# sch.net
KiCad netlist of a schematic drawn in Altium Designer
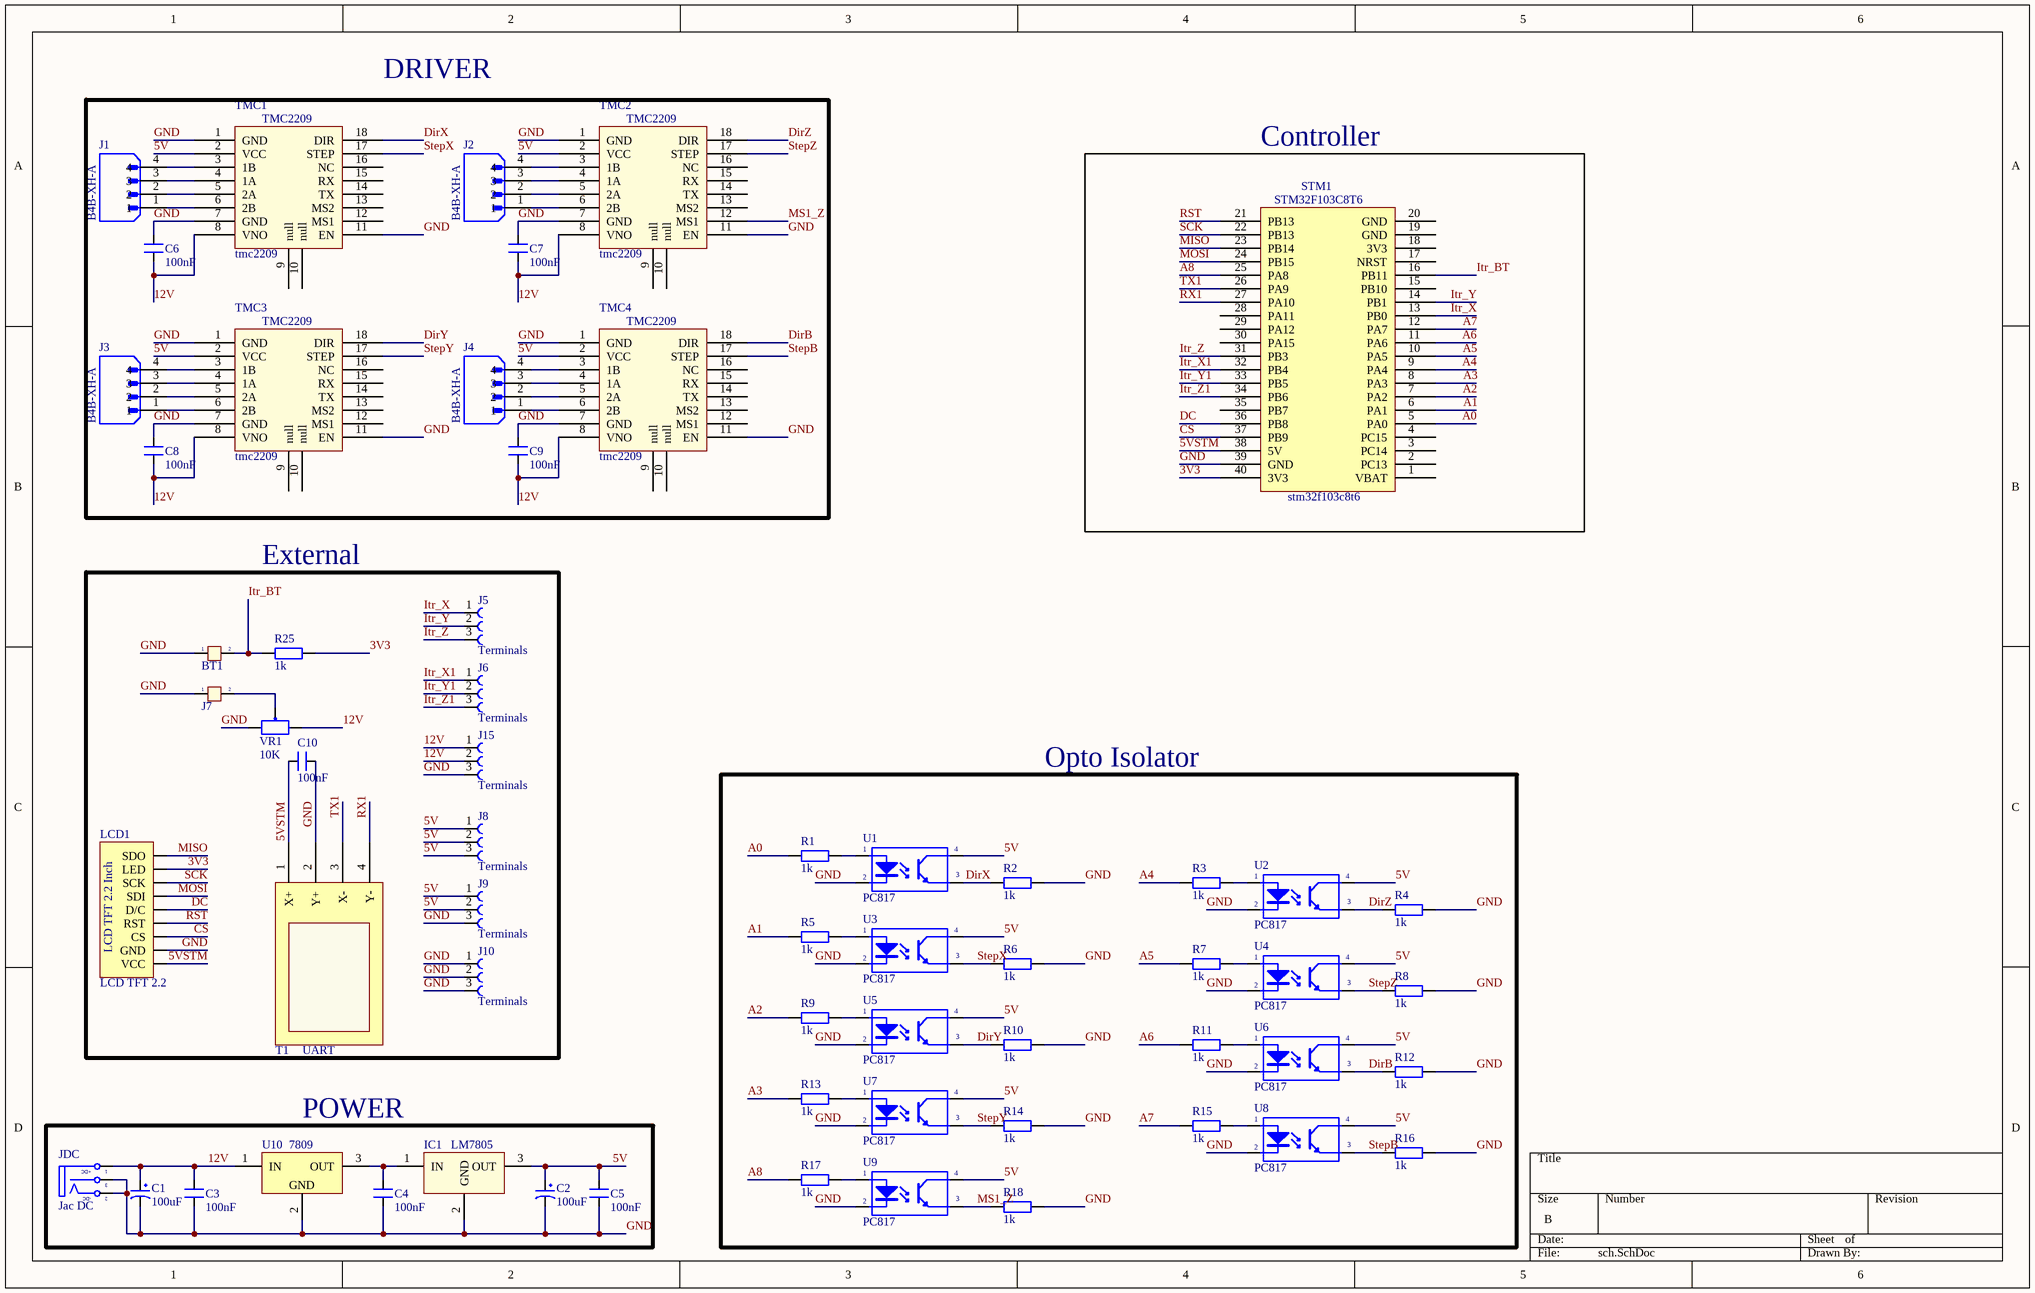
[diagram p0: sch.SchDoc]

(export (version "E")
  (design (tool "Eeschema 10.0.6"))
  (components
    (comp (ref "BT1") (value "Jumper 2") (footprint "jp2h") (libsource (lib "My Library") (part "JP 2")))
    (comp (ref "C1")
      (value "100uF")
      (footprint "CP1.5/3.4")
      (description "Cap 100uF/35V - 470uF/16V")
      (libsource (lib "My Library") (part "CP3"))
    )
    (comp (ref "C2")
      (value "100uF")
      (footprint "CP1.5/3.4")
      (description "Cap 100uF/35V - 470uF/16V")
      (libsource (lib "My Library") (part "CP3"))
    )
    (comp (ref "C3")
      (value "100nF")
      (footprint "CN2")
      (description "Cap np 104 => 105pF")
      (libsource (lib "My Library") (part "CN2"))
    )
    (comp (ref "C4")
      (value "100nF")
      (footprint "CN2")
      (description "Cap np 104 => 105pF")
      (libsource (lib "My Library") (part "CN2"))
    )
    (comp (ref "C5")
      (value "100nF")
      (footprint "CN2")
      (description "Cap np 104 => 105pF")
      (libsource (lib "My Library") (part "CN2"))
    )
    (comp (ref "C6")
      (value "100nF")
      (footprint "CN2")
      (description "Cap np 104 => 105pF")
      (libsource (lib "My Library") (part "CN2"))
    )
    (comp (ref "C7")
      (value "100nF")
      (footprint "CN2")
      (description "Cap np 104 => 105pF")
      (libsource (lib "My Library") (part "CN2"))
    )
    (comp (ref "C8")
      (value "100nF")
      (footprint "CN2")
      (description "Cap np 104 => 105pF")
      (libsource (lib "My Library") (part "CN2"))
    )
    (comp (ref "C9")
      (value "100nF")
      (footprint "CN2")
      (description "Cap np 104 => 105pF")
      (libsource (lib "My Library") (part "CN2"))
    )
    (comp (ref "C10")
      (value "100nF")
      (footprint "CN2")
      (description "Cap np 104 => 105pF")
      (libsource (lib "My Library") (part "CN2"))
    )
    (comp (ref "IC1")
      (value "LM7805")
      (footprint "QTO-220")
      (description "On ap +, from + 5 to + 24VDC")
      (libsource (lib "My Library") (part "LM78xx"))
    )
    (comp (ref "J1")
      (value "B4B-XH-A")
      (footprint "JST_B4B-XH-A(LF)(SN)")
      (fields (field (name "MP") "B4B-XH-A(LF)(SN)"))
      (libsource (lib "B4B-XH-A_LF__SN_") (part "B4B-XH-A(LF)(SN)"))
    )
    (comp (ref "J2")
      (value "B4B-XH-A")
      (footprint "JST_B4B-XH-A(LF)(SN)")
      (fields (field (name "MP") "B4B-XH-A(LF)(SN)"))
      (libsource (lib "B4B-XH-A_LF__SN_") (part "B4B-XH-A(LF)(SN)"))
    )
    (comp (ref "J3")
      (value "B4B-XH-A")
      (footprint "JST_B4B-XH-A(LF)(SN)")
      (fields (field (name "MP") "B4B-XH-A(LF)(SN)"))
      (libsource (lib "B4B-XH-A_LF__SN_") (part "B4B-XH-A(LF)(SN)"))
    )
    (comp (ref "J4")
      (value "B4B-XH-A")
      (footprint "JST_B4B-XH-A(LF)(SN)")
      (fields (field (name "MP") "B4B-XH-A(LF)(SN)"))
      (libsource (lib "B4B-XH-A_LF__SN_") (part "B4B-XH-A(LF)(SN)"))
    )
    (comp (ref "J5")
      (value "Terminals")
      (footprint "691214110003")
      (description "3 Position Wire to Board Terminal Block Horizontal with Board 0.138 (3.50mm) Through Hole")
      (fields (field (name "MP") "691214110003") (field (name "MF") "Wurth Elektronik"))
      (libsource (lib "691214110003") (part "691214110003"))
    )
    (comp (ref "J6")
      (value "Terminals")
      (footprint "691214110003")
      (description "3 Position Wire to Board Terminal Block Horizontal with Board 0.138 (3.50mm) Through Hole")
      (fields (field (name "MP") "691214110003") (field (name "MF") "Wurth Elektronik"))
      (libsource (lib "691214110003") (part "691214110003"))
    )
    (comp (ref "J7") (value "Jumper 2") (footprint "jp2h") (libsource (lib "syhaunguyen") (part "JP 2")))
    (comp (ref "J8")
      (value "Terminals")
      (footprint "691214110003")
      (description "3 Position Wire to Board Terminal Block Horizontal with Board 0.138 (3.50mm) Through Hole")
      (fields (field (name "MP") "691214110003") (field (name "MF") "Wurth Elektronik"))
      (libsource (lib "691214110003") (part "691214110003"))
    )
    (comp (ref "J9")
      (value "Terminals")
      (footprint "691214110003")
      (description "3 Position Wire to Board Terminal Block Horizontal with Board 0.138 (3.50mm) Through Hole")
      (fields (field (name "MP") "691214110003") (field (name "MF") "Wurth Elektronik"))
      (libsource (lib "691214110003") (part "691214110003"))
    )
    (comp (ref "J10")
      (value "Terminals")
      (footprint "691214110003")
      (description "3 Position Wire to Board Terminal Block Horizontal with Board 0.138 (3.50mm) Through Hole")
      (fields (field (name "MP") "691214110003") (field (name "MF") "Wurth Elektronik"))
      (libsource (lib "691214110003") (part "691214110003"))
    )
    (comp (ref "J15")
      (value "Terminals")
      (footprint "691214110003")
      (description "3 Position Wire to Board Terminal Block Horizontal with Board 0.138 (3.50mm) Through Hole")
      (fields (field (name "MP") "691214110003") (field (name "MF") "Wurth Elektronik"))
      (libsource (lib "691214110003") (part "691214110003"))
    )
    (comp (ref "JDC")
      (value "Jac DC")
      (footprint "DC-IN")
      (description "Jac DC input")
      (libsource (lib "My Library") (part "DCIN"))
    )
    (comp (ref "LCD1")
      (value "LCD TFT 2.2")
      (footprint "JP9-C1T")
      (fields
        (field (name "MANUFACTURER") "Würth Elektronik eiSos GmbH")
        (field (name "PARTNO") "613009143121")
        (field (name "CREATED BY") "Karrer Zheng")
      )
      (libsource (lib "My Library") (part "LCD TFT 2.2"))
    )
    (comp (ref "R1")
      (value "1k")
      (footprint "R1/4W")
      (description "Resistor 1/4W")
      (libsource (lib "My Library") (part "R1/4W"))
    )
    (comp (ref "R2")
      (value "1k")
      (footprint "R1/4W")
      (description "Resistor 1/4W")
      (libsource (lib "My Library") (part "R1/4W"))
    )
    (comp (ref "R3")
      (value "1k")
      (footprint "R1/4W")
      (description "Resistor 1/4W")
      (libsource (lib "My Library") (part "R1/4W"))
    )
    (comp (ref "R4")
      (value "1k")
      (footprint "R1/4W")
      (description "Resistor 1/4W")
      (libsource (lib "My Library") (part "R1/4W"))
    )
    (comp (ref "R5")
      (value "1k")
      (footprint "R1/4W")
      (description "Resistor 1/4W")
      (libsource (lib "My Library") (part "R1/4W"))
    )
    (comp (ref "R6")
      (value "1k")
      (footprint "R1/4W")
      (description "Resistor 1/4W")
      (libsource (lib "My Library") (part "R1/4W"))
    )
    (comp (ref "R7")
      (value "1k")
      (footprint "R1/4W")
      (description "Resistor 1/4W")
      (libsource (lib "My Library") (part "R1/4W"))
    )
    (comp (ref "R8")
      (value "1k")
      (footprint "R1/4W")
      (description "Resistor 1/4W")
      (libsource (lib "My Library") (part "R1/4W"))
    )
    (comp (ref "R9")
      (value "1k")
      (footprint "R1/4W")
      (description "Resistor 1/4W")
      (libsource (lib "My Library") (part "R1/4W"))
    )
    (comp (ref "R10")
      (value "1k")
      (footprint "R1/4W")
      (description "Resistor 1/4W")
      (libsource (lib "My Library") (part "R1/4W"))
    )
    (comp (ref "R11")
      (value "1k")
      (footprint "R1/4W")
      (description "Resistor 1/4W")
      (libsource (lib "My Library") (part "R1/4W"))
    )
    (comp (ref "R12")
      (value "1k")
      (footprint "R1/4W")
      (description "Resistor 1/4W")
      (libsource (lib "My Library") (part "R1/4W"))
    )
    (comp (ref "R13")
      (value "1k")
      (footprint "R1/4W")
      (description "Resistor 1/4W")
      (libsource (lib "My Library") (part "R1/4W"))
    )
    (comp (ref "R14")
      (value "1k")
      (footprint "R1/4W")
      (description "Resistor 1/4W")
      (libsource (lib "My Library") (part "R1/4W"))
    )
    (comp (ref "R15")
      (value "1k")
      (footprint "R1/4W")
      (description "Resistor 1/4W")
      (libsource (lib "My Library") (part "R1/4W"))
    )
    (comp (ref "R16")
      (value "1k")
      (footprint "R1/4W")
      (description "Resistor 1/4W")
      (libsource (lib "My Library") (part "R1/4W"))
    )
    (comp (ref "R17")
      (value "1k")
      (footprint "R1/4W")
      (description "Resistor 1/4W")
      (libsource (lib "My Library") (part "R1/4W"))
    )
    (comp (ref "R18")
      (value "1k")
      (footprint "R1/4W")
      (description "Resistor 1/4W")
      (libsource (lib "My Library") (part "R1/4W"))
    )
    (comp (ref "R25")
      (value "1k")
      (footprint "R1/4W")
      (description "Resistor 1/4W")
      (libsource (lib "My Library") (part "R1/4W"))
    )
    (comp (ref "STM1")
      (value "stm32f103c8t6")
      (footprint "STM32F103")
      (libsource (lib "STM32F103") (part "STM32F103"))
    )
    (comp (ref "T1")
      (value "UART")
      (footprint "HDR1X4H")
      (description "4 wires")
      (fields (field (name "CREATOR") "Nguyen Ba Bien"))
      (libsource (lib "My Library") (part "TouchPanel"))
    )
    (comp (ref "TMC1")
      (value "tmc2209")
      (footprint "TMC2209")
      (libsource (lib "tmc2209") (part "Driver_TMC2209"))
    )
    (comp (ref "TMC2")
      (value "tmc2209")
      (footprint "TMC2209")
      (libsource (lib "tmc2209") (part "Driver_TMC2209"))
    )
    (comp (ref "TMC3")
      (value "tmc2209")
      (footprint "TMC2209")
      (libsource (lib "tmc2209") (part "Driver_TMC2209"))
    )
    (comp (ref "TMC4")
      (value "tmc2209")
      (footprint "TMC2209")
      (libsource (lib "tmc2209") (part "Driver_TMC2209"))
    )
    (comp (ref "U1")
      (value "PC817")
      (footprint "DIP4/W0.3")
      (description "Single Opto")
      (libsource (lib "syhaunguyen") (part "PC817"))
    )
    (comp (ref "U2")
      (value "PC817")
      (footprint "DIP4/W0.3")
      (description "Single Opto")
      (libsource (lib "syhaunguyen") (part "PC817"))
    )
    (comp (ref "U3")
      (value "PC817")
      (footprint "DIP4/W0.3")
      (description "Single Opto")
      (libsource (lib "syhaunguyen") (part "PC817"))
    )
    (comp (ref "U4")
      (value "PC817")
      (footprint "DIP4/W0.3")
      (description "Single Opto")
      (libsource (lib "syhaunguyen") (part "PC817"))
    )
    (comp (ref "U5")
      (value "PC817")
      (footprint "DIP4/W0.3")
      (description "Single Opto")
      (libsource (lib "syhaunguyen") (part "PC817"))
    )
    (comp (ref "U6")
      (value "PC817")
      (footprint "DIP4/W0.3")
      (description "Single Opto")
      (libsource (lib "syhaunguyen") (part "PC817"))
    )
    (comp (ref "U7")
      (value "PC817")
      (footprint "DIP4/W0.3")
      (description "Single Opto")
      (libsource (lib "syhaunguyen") (part "PC817"))
    )
    (comp (ref "U8")
      (value "PC817")
      (footprint "DIP4/W0.3")
      (description "Single Opto")
      (libsource (lib "syhaunguyen") (part "PC817"))
    )
    (comp (ref "U9")
      (value "PC817")
      (footprint "DIP4/W0.3")
      (description "Single Opto")
      (libsource (lib "syhaunguyen") (part "PC817"))
    )
    (comp (ref "U10")
      (value "7809")
      (footprint "HDR1x3 BIG")
      (description "Positive Voltage Regulator")
      (fields (field (name "PUBLISHER") "Altium Limited"))
      (libsource (lib "My Library") (part "7809"))
    )
    (comp (ref "VR1")
      (value "10K")
      (footprint "VR")
      (description "Var Resistor")
      (libsource (lib "syhaunguyen") (part "VR"))
    )
  )
  (nets
    (net (code "1") (name "/3V3") (class "Default")
      (node (ref "LCD1") (pin "8") (pinfunction "LED_8") (pintype "passive"))
      (node (ref "R25") (pin "2") (pinfunction "2_2") (pintype "passive"))
      (node (ref "STM1") (pin "40") (pinfunction "3V3_40") (pintype "passive"))
    )
    (net (code "2") (name "/5V") (class "Default")
      (node (ref "C2") (pin "1") (pinfunction "1_1") (pintype "passive"))
      (node (ref "C5") (pin "2") (pinfunction "2_2") (pintype "passive"))
      (node (ref "IC1") (pin "3") (pinfunction "OUT_3") (pintype "passive"))
      (node (ref "J8") (pin "1") (pinfunction "1_1") (pintype "passive"))
      (node (ref "J8") (pin "2") (pinfunction "2_2") (pintype "passive"))
      (node (ref "J8") (pin "3") (pinfunction "3_3") (pintype "passive"))
      (node (ref "J9") (pin "1") (pinfunction "1_1") (pintype "passive"))
      (node (ref "J9") (pin "2") (pinfunction "2_2") (pintype "passive"))
      (node (ref "TMC1") (pin "2") (pinfunction "VCC_2") (pintype "passive"))
      (node (ref "TMC2") (pin "2") (pinfunction "VCC_2") (pintype "passive"))
      (node (ref "TMC3") (pin "2") (pinfunction "VCC_2") (pintype "passive"))
      (node (ref "TMC4") (pin "2") (pinfunction "VCC_2") (pintype "passive"))
      (node (ref "U1") (pin "4") (pinfunction "C_4") (pintype "passive"))
      (node (ref "U2") (pin "4") (pinfunction "C_4") (pintype "passive"))
      (node (ref "U3") (pin "4") (pinfunction "C_4") (pintype "passive"))
      (node (ref "U4") (pin "4") (pinfunction "C_4") (pintype "passive"))
      (node (ref "U5") (pin "4") (pinfunction "C_4") (pintype "passive"))
      (node (ref "U6") (pin "4") (pinfunction "C_4") (pintype "passive"))
      (node (ref "U7") (pin "4") (pinfunction "C_4") (pintype "passive"))
      (node (ref "U8") (pin "4") (pinfunction "C_4") (pintype "passive"))
      (node (ref "U9") (pin "4") (pinfunction "C_4") (pintype "passive"))
    )
    (net (code "3") (name "/5VSTM") (class "Default")
      (node (ref "C10") (pin "2") (pinfunction "2_2") (pintype "passive"))
      (node (ref "LCD1") (pin "1") (pinfunction "VCC_1") (pintype "passive"))
      (node (ref "STM1") (pin "38") (pinfunction "5V_38") (pintype "passive"))
      (node (ref "T1") (pin "1") (pinfunction "X+_1") (pintype "passive"))
    )
    (net (code "4") (name "/12V") (class "Default")
      (node (ref "C1") (pin "1") (pinfunction "1_1") (pintype "passive"))
      (node (ref "C3") (pin "2") (pinfunction "2_2") (pintype "passive"))
      (node (ref "C6") (pin "1") (pinfunction "1_1") (pintype "passive"))
      (node (ref "C7") (pin "1") (pinfunction "1_1") (pintype "passive"))
      (node (ref "C8") (pin "1") (pinfunction "1_1") (pintype "passive"))
      (node (ref "C9") (pin "1") (pinfunction "1_1") (pintype "passive"))
      (node (ref "J15") (pin "1") (pinfunction "1_1") (pintype "passive"))
      (node (ref "J15") (pin "2") (pinfunction "2_2") (pintype "passive"))
      (node (ref "JDC") (pin "1") (pinfunction "T_1") (pintype "passive"))
      (node (ref "TMC1") (pin "8") (pinfunction "VNO_8") (pintype "passive"))
      (node (ref "TMC2") (pin "8") (pinfunction "VNO_8") (pintype "passive"))
      (node (ref "TMC3") (pin "8") (pinfunction "VNO_8") (pintype "passive"))
      (node (ref "TMC4") (pin "8") (pinfunction "VNO_8") (pintype "passive"))
      (node (ref "U10") (pin "1") (pinfunction "IN_1") (pintype "power_in"))
      (node (ref "VR1") (pin "3") (pinfunction "3_3") (pintype "passive"))
    )
    (net (code "5") (name "/A0") (class "Default")
      (node (ref "R1") (pin "1") (pinfunction "1_1") (pintype "passive"))
      (node (ref "STM1") (pin "5") (pinfunction "PA0_5") (pintype "passive"))
    )
    (net (code "6") (name "/A1") (class "Default")
      (node (ref "R5") (pin "1") (pinfunction "1_1") (pintype "passive"))
      (node (ref "STM1") (pin "6") (pinfunction "PA1_6") (pintype "passive"))
    )
    (net (code "7") (name "/A2") (class "Default")
      (node (ref "R9") (pin "1") (pinfunction "1_1") (pintype "passive"))
      (node (ref "STM1") (pin "7") (pinfunction "PA2_7") (pintype "passive"))
    )
    (net (code "8") (name "/A3") (class "Default")
      (node (ref "R13") (pin "1") (pinfunction "1_1") (pintype "passive"))
      (node (ref "STM1") (pin "8") (pinfunction "PA3_8") (pintype "passive"))
    )
    (net (code "9") (name "/A4") (class "Default")
      (node (ref "R3") (pin "1") (pinfunction "1_1") (pintype "passive"))
      (node (ref "STM1") (pin "9") (pinfunction "PA4_9") (pintype "passive"))
    )
    (net (code "10") (name "/A5") (class "Default")
      (node (ref "R7") (pin "1") (pinfunction "1_1") (pintype "passive"))
      (node (ref "STM1") (pin "10") (pinfunction "PA5_10") (pintype "passive"))
    )
    (net (code "11") (name "/A6") (class "Default")
      (node (ref "R11") (pin "1") (pinfunction "1_1") (pintype "passive"))
      (node (ref "STM1") (pin "11") (pinfunction "PA6_11") (pintype "passive"))
    )
    (net (code "12") (name "/A7") (class "Default")
      (node (ref "R15") (pin "1") (pinfunction "1_1") (pintype "passive"))
      (node (ref "STM1") (pin "12") (pinfunction "PA7_12") (pintype "passive"))
    )
    (net (code "13") (name "/A8") (class "Default")
      (node (ref "R17") (pin "1") (pinfunction "1_1") (pintype "passive"))
      (node (ref "STM1") (pin "25") (pinfunction "PA8_25") (pintype "passive"))
    )
    (net (code "14") (name "/CS") (class "Default")
      (node (ref "LCD1") (pin "3") (pinfunction "CS_3") (pintype "passive"))
      (node (ref "STM1") (pin "37") (pinfunction "PB9_37") (pintype "passive"))
    )
    (net (code "15") (name "/DC") (class "Default")
      (node (ref "LCD1") (pin "5") (pinfunction "D/C_5") (pintype "passive"))
      (node (ref "STM1") (pin "36") (pinfunction "PB8_36") (pintype "passive"))
    )
    (net (code "16") (name "/DirB") (class "Default")
      (node (ref "R12") (pin "1") (pinfunction "1_1") (pintype "passive"))
      (node (ref "TMC4") (pin "18") (pinfunction "DIR_18") (pintype "passive"))
      (node (ref "U6") (pin "3") (pinfunction "E_3") (pintype "passive"))
    )
    (net (code "17") (name "/DirX") (class "Default")
      (node (ref "R2") (pin "1") (pinfunction "1_1") (pintype "passive"))
      (node (ref "TMC1") (pin "18") (pinfunction "DIR_18") (pintype "passive"))
      (node (ref "U1") (pin "3") (pinfunction "E_3") (pintype "passive"))
    )
    (net (code "18") (name "/DirY") (class "Default")
      (node (ref "R10") (pin "1") (pinfunction "1_1") (pintype "passive"))
      (node (ref "TMC3") (pin "18") (pinfunction "DIR_18") (pintype "passive"))
      (node (ref "U5") (pin "3") (pinfunction "E_3") (pintype "passive"))
    )
    (net (code "19") (name "/DirZ") (class "Default")
      (node (ref "R4") (pin "1") (pinfunction "1_1") (pintype "passive"))
      (node (ref "TMC2") (pin "18") (pinfunction "DIR_18") (pintype "passive"))
      (node (ref "U2") (pin "3") (pinfunction "E_3") (pintype "passive"))
    )
    (net (code "20") (name "/GND") (class "Default")
      (node (ref "BT1") (pin "1") (pinfunction "1_1") (pintype "passive"))
      (node (ref "C1") (pin "2") (pinfunction "2_2") (pintype "passive"))
      (node (ref "C10") (pin "1") (pinfunction "1_1") (pintype "passive"))
      (node (ref "C2") (pin "2") (pinfunction "2_2") (pintype "passive"))
      (node (ref "C3") (pin "1") (pinfunction "1_1") (pintype "passive"))
      (node (ref "C4") (pin "1") (pinfunction "1_1") (pintype "passive"))
      (node (ref "C5") (pin "1") (pinfunction "1_1") (pintype "passive"))
      (node (ref "C6") (pin "2") (pinfunction "2_2") (pintype "passive"))
      (node (ref "C7") (pin "2") (pinfunction "2_2") (pintype "passive"))
      (node (ref "C8") (pin "2") (pinfunction "2_2") (pintype "passive"))
      (node (ref "C9") (pin "2") (pinfunction "2_2") (pintype "passive"))
      (node (ref "IC1") (pin "2") (pinfunction "GND_2") (pintype "passive"))
      (node (ref "J10") (pin "1") (pinfunction "1_1") (pintype "passive"))
      (node (ref "J10") (pin "2") (pinfunction "2_2") (pintype "passive"))
      (node (ref "J10") (pin "3") (pinfunction "3_3") (pintype "passive"))
      (node (ref "J15") (pin "3") (pinfunction "3_3") (pintype "passive"))
      (node (ref "J7") (pin "1") (pinfunction "1_1") (pintype "passive"))
      (node (ref "J9") (pin "3") (pinfunction "3_3") (pintype "passive"))
      (node (ref "JDC") (pin "2") (pinfunction "TN_2") (pintype "passive"))
      (node (ref "JDC") (pin "3") (pinfunction "S_3") (pintype "power_in"))
      (node (ref "LCD1") (pin "2") (pinfunction "GND_2") (pintype "passive"))
      (node (ref "R10") (pin "2") (pinfunction "2_2") (pintype "passive"))
      (node (ref "R12") (pin "2") (pinfunction "2_2") (pintype "passive"))
      (node (ref "R14") (pin "2") (pinfunction "2_2") (pintype "passive"))
      (node (ref "R16") (pin "2") (pinfunction "2_2") (pintype "passive"))
      (node (ref "R18") (pin "2") (pinfunction "2_2") (pintype "passive"))
      (node (ref "R2") (pin "2") (pinfunction "2_2") (pintype "passive"))
      (node (ref "R4") (pin "2") (pinfunction "2_2") (pintype "passive"))
      (node (ref "R6") (pin "2") (pinfunction "2_2") (pintype "passive"))
      (node (ref "R8") (pin "2") (pinfunction "2_2") (pintype "passive"))
      (node (ref "STM1") (pin "39") (pinfunction "GND_39") (pintype "passive"))
      (node (ref "T1") (pin "2") (pinfunction "Y+_2") (pintype "passive"))
      (node (ref "TMC1") (pin "1") (pinfunction "GND_1") (pintype "passive"))
      (node (ref "TMC1") (pin "11") (pinfunction "EN_11") (pintype "passive"))
      (node (ref "TMC1") (pin "7") (pinfunction "GND_7") (pintype "passive"))
      (node (ref "TMC2") (pin "1") (pinfunction "GND_1") (pintype "passive"))
      (node (ref "TMC2") (pin "11") (pinfunction "EN_11") (pintype "passive"))
      (node (ref "TMC2") (pin "7") (pinfunction "GND_7") (pintype "passive"))
      (node (ref "TMC3") (pin "1") (pinfunction "GND_1") (pintype "passive"))
      (node (ref "TMC3") (pin "11") (pinfunction "EN_11") (pintype "passive"))
      (node (ref "TMC3") (pin "7") (pinfunction "GND_7") (pintype "passive"))
      (node (ref "TMC4") (pin "1") (pinfunction "GND_1") (pintype "passive"))
      (node (ref "TMC4") (pin "11") (pinfunction "EN_11") (pintype "passive"))
      (node (ref "TMC4") (pin "7") (pinfunction "GND_7") (pintype "passive"))
      (node (ref "U1") (pin "2") (pinfunction "K_2") (pintype "passive"))
      (node (ref "U10") (pin "2") (pinfunction "GND_2") (pintype "power_in"))
      (node (ref "U2") (pin "2") (pinfunction "K_2") (pintype "passive"))
      (node (ref "U3") (pin "2") (pinfunction "K_2") (pintype "passive"))
      (node (ref "U4") (pin "2") (pinfunction "K_2") (pintype "passive"))
      (node (ref "U5") (pin "2") (pinfunction "K_2") (pintype "passive"))
      (node (ref "U6") (pin "2") (pinfunction "K_2") (pintype "passive"))
      (node (ref "U7") (pin "2") (pinfunction "K_2") (pintype "passive"))
      (node (ref "U8") (pin "2") (pinfunction "K_2") (pintype "passive"))
      (node (ref "U9") (pin "2") (pinfunction "K_2") (pintype "passive"))
      (node (ref "VR1") (pin "1") (pinfunction "1_1") (pintype "passive"))
    )
    (net (code "21") (name "/Itr_BT") (class "Default")
      (node (ref "BT1") (pin "2") (pinfunction "2_2") (pintype "passive"))
      (node (ref "R25") (pin "1") (pinfunction "1_1") (pintype "passive"))
      (node (ref "STM1") (pin "16") (pinfunction "PB11_16") (pintype "passive"))
    )
    (net (code "22") (name "/Itr_X") (class "Default")
      (node (ref "J5") (pin "1") (pinfunction "1_1") (pintype "passive"))
      (node (ref "STM1") (pin "13") (pinfunction "PB0_13") (pintype "passive"))
    )
    (net (code "23") (name "/Itr_X1") (class "Default")
      (node (ref "J6") (pin "1") (pinfunction "1_1") (pintype "passive"))
      (node (ref "STM1") (pin "32") (pinfunction "PB4_32") (pintype "passive"))
    )
    (net (code "24") (name "/Itr_Y") (class "Default")
      (node (ref "J5") (pin "2") (pinfunction "2_2") (pintype "passive"))
      (node (ref "STM1") (pin "14") (pinfunction "PB1_14") (pintype "passive"))
    )
    (net (code "25") (name "/Itr_Y1") (class "Default")
      (node (ref "J6") (pin "2") (pinfunction "2_2") (pintype "passive"))
      (node (ref "STM1") (pin "33") (pinfunction "PB5_33") (pintype "passive"))
    )
    (net (code "26") (name "/Itr_Z") (class "Default")
      (node (ref "J5") (pin "3") (pinfunction "3_3") (pintype "passive"))
      (node (ref "STM1") (pin "31") (pinfunction "PB3_31") (pintype "passive"))
    )
    (net (code "27") (name "/Itr_Z1") (class "Default")
      (node (ref "J6") (pin "3") (pinfunction "3_3") (pintype "passive"))
      (node (ref "STM1") (pin "34") (pinfunction "PB6_34") (pintype "passive"))
    )
    (net (code "28") (name "/MISO") (class "Default")
      (node (ref "LCD1") (pin "9") (pinfunction "SDO_9") (pintype "passive"))
      (node (ref "STM1") (pin "23") (pinfunction "PB14_23") (pintype "passive"))
    )
    (net (code "29") (name "/MOSI") (class "Default")
      (node (ref "LCD1") (pin "6") (pinfunction "SDI_6") (pintype "passive"))
      (node (ref "STM1") (pin "24") (pinfunction "PB15_24") (pintype "passive"))
    )
    (net (code "30") (name "/MS1_Z") (class "Default")
      (node (ref "R18") (pin "1") (pinfunction "1_1") (pintype "passive"))
      (node (ref "TMC2") (pin "12") (pinfunction "MS1_12") (pintype "passive"))
      (node (ref "U9") (pin "3") (pinfunction "E_3") (pintype "passive"))
    )
    (net (code "31") (name "/RST") (class "Default")
      (node (ref "LCD1") (pin "4") (pinfunction "RST_4") (pintype "passive"))
      (node (ref "STM1") (pin "21") (pinfunction "PB13_21") (pintype "passive"))
    )
    (net (code "32") (name "/RX1") (class "Default")
      (node (ref "STM1") (pin "27") (pinfunction "PA10_27") (pintype "passive"))
      (node (ref "T1") (pin "4") (pinfunction "Y-_4") (pintype "passive"))
    )
    (net (code "33") (name "/SCK") (class "Default")
      (node (ref "LCD1") (pin "7") (pinfunction "SCK_7") (pintype "passive"))
      (node (ref "STM1") (pin "22") (pinfunction "PB13_22") (pintype "passive"))
    )
    (net (code "34") (name "/StepB") (class "Default")
      (node (ref "R16") (pin "1") (pinfunction "1_1") (pintype "passive"))
      (node (ref "TMC4") (pin "17") (pinfunction "STEP_17") (pintype "passive"))
      (node (ref "U8") (pin "3") (pinfunction "E_3") (pintype "passive"))
    )
    (net (code "35") (name "/StepX") (class "Default")
      (node (ref "R6") (pin "1") (pinfunction "1_1") (pintype "passive"))
      (node (ref "TMC1") (pin "17") (pinfunction "STEP_17") (pintype "passive"))
      (node (ref "U3") (pin "3") (pinfunction "E_3") (pintype "passive"))
    )
    (net (code "36") (name "/StepY") (class "Default")
      (node (ref "R14") (pin "1") (pinfunction "1_1") (pintype "passive"))
      (node (ref "TMC3") (pin "17") (pinfunction "STEP_17") (pintype "passive"))
      (node (ref "U7") (pin "3") (pinfunction "E_3") (pintype "passive"))
    )
    (net (code "37") (name "/StepZ") (class "Default")
      (node (ref "R8") (pin "1") (pinfunction "1_1") (pintype "passive"))
      (node (ref "TMC2") (pin "17") (pinfunction "STEP_17") (pintype "passive"))
      (node (ref "U4") (pin "3") (pinfunction "E_3") (pintype "passive"))
    )
    (net (code "38") (name "/TX1") (class "Default")
      (node (ref "STM1") (pin "26") (pinfunction "PA9_26") (pintype "passive"))
      (node (ref "T1") (pin "3") (pinfunction "X-_3") (pintype "passive"))
    )
    (net (code "39") (name "Net-(IC1-IN)") (class "Default")
      (node (ref "C4") (pin "2") (pinfunction "2_2") (pintype "passive"))
      (node (ref "IC1") (pin "1") (pinfunction "IN_1") (pintype "passive"))
      (node (ref "U10") (pin "3") (pinfunction "OUT_3") (pintype "power_in"))
    )
    (net (code "40") (name "Net-(J7-Pad2)") (class "Default")
      (node (ref "J7") (pin "2") (pinfunction "2_2") (pintype "passive"))
      (node (ref "VR1") (pin "2") (pinfunction "2_2") (pintype "passive"))
    )
    (net (code "41") (name "Net-(TMC1-1A)") (class "Default")
      (node (ref "J1") (pin "3") (pinfunction "3_3") (pintype "passive"))
      (node (ref "TMC1") (pin "4") (pinfunction "1A_4") (pintype "passive"))
    )
    (net (code "42") (name "Net-(TMC1-1B)") (class "Default")
      (node (ref "J1") (pin "4") (pinfunction "4_4") (pintype "passive"))
      (node (ref "TMC1") (pin "3") (pinfunction "1B_3") (pintype "passive"))
    )
    (net (code "43") (name "Net-(TMC1-2A)") (class "Default")
      (node (ref "J1") (pin "2") (pinfunction "2_2") (pintype "passive"))
      (node (ref "TMC1") (pin "5") (pinfunction "2A_5") (pintype "passive"))
    )
    (net (code "44") (name "Net-(TMC1-2B)") (class "Default")
      (node (ref "J1") (pin "1") (pinfunction "1_1") (pintype "passive"))
      (node (ref "TMC1") (pin "6") (pinfunction "2B_6") (pintype "passive"))
    )
    (net (code "45") (name "Net-(TMC2-1A)") (class "Default")
      (node (ref "J2") (pin "3") (pinfunction "3_3") (pintype "passive"))
      (node (ref "TMC2") (pin "4") (pinfunction "1A_4") (pintype "passive"))
    )
    (net (code "46") (name "Net-(TMC2-1B)") (class "Default")
      (node (ref "J2") (pin "4") (pinfunction "4_4") (pintype "passive"))
      (node (ref "TMC2") (pin "3") (pinfunction "1B_3") (pintype "passive"))
    )
    (net (code "47") (name "Net-(TMC2-2A)") (class "Default")
      (node (ref "J2") (pin "2") (pinfunction "2_2") (pintype "passive"))
      (node (ref "TMC2") (pin "5") (pinfunction "2A_5") (pintype "passive"))
    )
    (net (code "48") (name "Net-(TMC2-2B)") (class "Default")
      (node (ref "J2") (pin "1") (pinfunction "1_1") (pintype "passive"))
      (node (ref "TMC2") (pin "6") (pinfunction "2B_6") (pintype "passive"))
    )
    (net (code "49") (name "Net-(TMC3-1A)") (class "Default")
      (node (ref "J3") (pin "3") (pinfunction "3_3") (pintype "passive"))
      (node (ref "TMC3") (pin "4") (pinfunction "1A_4") (pintype "passive"))
    )
    (net (code "50") (name "Net-(TMC3-1B)") (class "Default")
      (node (ref "J3") (pin "4") (pinfunction "4_4") (pintype "passive"))
      (node (ref "TMC3") (pin "3") (pinfunction "1B_3") (pintype "passive"))
    )
    (net (code "51") (name "Net-(TMC3-2A)") (class "Default")
      (node (ref "J3") (pin "2") (pinfunction "2_2") (pintype "passive"))
      (node (ref "TMC3") (pin "5") (pinfunction "2A_5") (pintype "passive"))
    )
    (net (code "52") (name "Net-(TMC3-2B)") (class "Default")
      (node (ref "J3") (pin "1") (pinfunction "1_1") (pintype "passive"))
      (node (ref "TMC3") (pin "6") (pinfunction "2B_6") (pintype "passive"))
    )
    (net (code "53") (name "Net-(TMC4-1A)") (class "Default")
      (node (ref "J4") (pin "3") (pinfunction "3_3") (pintype "passive"))
      (node (ref "TMC4") (pin "4") (pinfunction "1A_4") (pintype "passive"))
    )
    (net (code "54") (name "Net-(TMC4-1B)") (class "Default")
      (node (ref "J4") (pin "4") (pinfunction "4_4") (pintype "passive"))
      (node (ref "TMC4") (pin "3") (pinfunction "1B_3") (pintype "passive"))
    )
    (net (code "55") (name "Net-(TMC4-2A)") (class "Default")
      (node (ref "J4") (pin "2") (pinfunction "2_2") (pintype "passive"))
      (node (ref "TMC4") (pin "5") (pinfunction "2A_5") (pintype "passive"))
    )
    (net (code "56") (name "Net-(TMC4-2B)") (class "Default")
      (node (ref "J4") (pin "1") (pinfunction "1_1") (pintype "passive"))
      (node (ref "TMC4") (pin "6") (pinfunction "2B_6") (pintype "passive"))
    )
    (net (code "57") (name "Net-(U1-A)") (class "Default")
      (node (ref "R1") (pin "2") (pinfunction "2_2") (pintype "passive"))
      (node (ref "U1") (pin "1") (pinfunction "A_1") (pintype "passive"))
    )
    (net (code "58") (name "Net-(U2-A)") (class "Default")
      (node (ref "R3") (pin "2") (pinfunction "2_2") (pintype "passive"))
      (node (ref "U2") (pin "1") (pinfunction "A_1") (pintype "passive"))
    )
    (net (code "59") (name "Net-(U3-A)") (class "Default")
      (node (ref "R5") (pin "2") (pinfunction "2_2") (pintype "passive"))
      (node (ref "U3") (pin "1") (pinfunction "A_1") (pintype "passive"))
    )
    (net (code "60") (name "Net-(U4-A)") (class "Default")
      (node (ref "R7") (pin "2") (pinfunction "2_2") (pintype "passive"))
      (node (ref "U4") (pin "1") (pinfunction "A_1") (pintype "passive"))
    )
    (net (code "61") (name "Net-(U5-A)") (class "Default")
      (node (ref "R9") (pin "2") (pinfunction "2_2") (pintype "passive"))
      (node (ref "U5") (pin "1") (pinfunction "A_1") (pintype "passive"))
    )
    (net (code "62") (name "Net-(U6-A)") (class "Default")
      (node (ref "R11") (pin "2") (pinfunction "2_2") (pintype "passive"))
      (node (ref "U6") (pin "1") (pinfunction "A_1") (pintype "passive"))
    )
    (net (code "63") (name "Net-(U7-A)") (class "Default")
      (node (ref "R13") (pin "2") (pinfunction "2_2") (pintype "passive"))
      (node (ref "U7") (pin "1") (pinfunction "A_1") (pintype "passive"))
    )
    (net (code "64") (name "Net-(U8-A)") (class "Default")
      (node (ref "R15") (pin "2") (pinfunction "2_2") (pintype "passive"))
      (node (ref "U8") (pin "1") (pinfunction "A_1") (pintype "passive"))
    )
    (net (code "65") (name "Net-(U9-A)") (class "Default")
      (node (ref "R17") (pin "2") (pinfunction "2_2") (pintype "passive"))
      (node (ref "U9") (pin "1") (pinfunction "A_1") (pintype "passive"))
    )
    (net (code "66") (name "unconnected-(STM1-3V3-Pad18)") (class "Default")
      (node (ref "STM1") (pin "18") (pinfunction "3V3_18") (pintype "passive"))
    )
    (net (code "67") (name "unconnected-(STM1-GND-Pad19)") (class "Default")
      (node (ref "STM1") (pin "19") (pinfunction "GND_19") (pintype "passive"))
    )
    (net (code "68") (name "unconnected-(STM1-GND-Pad20)") (class "Default")
      (node (ref "STM1") (pin "20") (pinfunction "GND_20") (pintype "passive"))
    )
    (net (code "69") (name "unconnected-(STM1-NRST-Pad17)") (class "Default")
      (node (ref "STM1") (pin "17") (pinfunction "NRST_17") (pintype "passive"))
    )
    (net (code "70") (name "unconnected-(STM1-PA11-Pad28)") (class "Default")
      (node (ref "STM1") (pin "28") (pinfunction "PA11_28") (pintype "passive"))
    )
    (net (code "71") (name "unconnected-(STM1-PA12-Pad29)") (class "Default")
      (node (ref "STM1") (pin "29") (pinfunction "PA12_29") (pintype "passive"))
    )
    (net (code "72") (name "unconnected-(STM1-PA15-Pad30)") (class "Default")
      (node (ref "STM1") (pin "30") (pinfunction "PA15_30") (pintype "passive"))
    )
    (net (code "73") (name "unconnected-(STM1-PB7-Pad35)") (class "Default")
      (node (ref "STM1") (pin "35") (pinfunction "PB7_35") (pintype "passive"))
    )
    (net (code "74") (name "unconnected-(STM1-PB10-Pad15)") (class "Default")
      (node (ref "STM1") (pin "15") (pinfunction "PB10_15") (pintype "passive"))
    )
    (net (code "75") (name "unconnected-(STM1-PC13-Pad2)") (class "Default")
      (node (ref "STM1") (pin "2") (pinfunction "PC13_2") (pintype "passive"))
    )
    (net (code "76") (name "unconnected-(STM1-PC14-Pad3)") (class "Default")
      (node (ref "STM1") (pin "3") (pinfunction "PC14_3") (pintype "passive"))
    )
    (net (code "77") (name "unconnected-(STM1-PC15-Pad4)") (class "Default")
      (node (ref "STM1") (pin "4") (pinfunction "PC15_4") (pintype "passive"))
    )
    (net (code "78") (name "unconnected-(STM1-VBAT-Pad1)") (class "Default")
      (node (ref "STM1") (pin "1") (pinfunction "VBAT_1") (pintype "passive"))
    )
    (net (code "79") (name "unconnected-(TMC1-MS1-Pad12)") (class "Default")
      (node (ref "TMC1") (pin "12") (pinfunction "MS1_12") (pintype "passive"))
    )
    (net (code "80") (name "unconnected-(TMC1-MS2-Pad13)") (class "Default")
      (node (ref "TMC1") (pin "13") (pinfunction "MS2_13") (pintype "passive"))
    )
    (net (code "81") (name "unconnected-(TMC1-NC-Pad16)") (class "Default")
      (node (ref "TMC1") (pin "16") (pinfunction "NC_16") (pintype "passive"))
    )
    (net (code "82") (name "unconnected-(TMC1-RX-Pad15)") (class "Default")
      (node (ref "TMC1") (pin "15") (pinfunction "RX_15") (pintype "passive"))
    )
    (net (code "83") (name "unconnected-(TMC1-TX-Pad14)") (class "Default")
      (node (ref "TMC1") (pin "14") (pinfunction "TX_14") (pintype "passive"))
    )
    (net (code "84") (name "unconnected-(TMC1-null-Pad9)") (class "Default")
      (node (ref "TMC1") (pin "9") (pinfunction "null_9") (pintype "passive"))
    )
    (net (code "85") (name "unconnected-(TMC1-null-Pad10)") (class "Default")
      (node (ref "TMC1") (pin "10") (pinfunction "null_10") (pintype "passive"))
    )
    (net (code "86") (name "unconnected-(TMC2-MS2-Pad13)") (class "Default")
      (node (ref "TMC2") (pin "13") (pinfunction "MS2_13") (pintype "passive"))
    )
    (net (code "87") (name "unconnected-(TMC2-NC-Pad16)") (class "Default")
      (node (ref "TMC2") (pin "16") (pinfunction "NC_16") (pintype "passive"))
    )
    (net (code "88") (name "unconnected-(TMC2-RX-Pad15)") (class "Default")
      (node (ref "TMC2") (pin "15") (pinfunction "RX_15") (pintype "passive"))
    )
    (net (code "89") (name "unconnected-(TMC2-TX-Pad14)") (class "Default")
      (node (ref "TMC2") (pin "14") (pinfunction "TX_14") (pintype "passive"))
    )
    (net (code "90") (name "unconnected-(TMC2-null-Pad9)") (class "Default")
      (node (ref "TMC2") (pin "9") (pinfunction "null_9") (pintype "passive"))
    )
    (net (code "91") (name "unconnected-(TMC2-null-Pad10)") (class "Default")
      (node (ref "TMC2") (pin "10") (pinfunction "null_10") (pintype "passive"))
    )
    (net (code "92") (name "unconnected-(TMC3-MS1-Pad12)") (class "Default")
      (node (ref "TMC3") (pin "12") (pinfunction "MS1_12") (pintype "passive"))
    )
    (net (code "93") (name "unconnected-(TMC3-MS2-Pad13)") (class "Default")
      (node (ref "TMC3") (pin "13") (pinfunction "MS2_13") (pintype "passive"))
    )
    (net (code "94") (name "unconnected-(TMC3-NC-Pad16)") (class "Default")
      (node (ref "TMC3") (pin "16") (pinfunction "NC_16") (pintype "passive"))
    )
    (net (code "95") (name "unconnected-(TMC3-RX-Pad15)") (class "Default")
      (node (ref "TMC3") (pin "15") (pinfunction "RX_15") (pintype "passive"))
    )
    (net (code "96") (name "unconnected-(TMC3-TX-Pad14)") (class "Default")
      (node (ref "TMC3") (pin "14") (pinfunction "TX_14") (pintype "passive"))
    )
    (net (code "97") (name "unconnected-(TMC3-null-Pad9)") (class "Default")
      (node (ref "TMC3") (pin "9") (pinfunction "null_9") (pintype "passive"))
    )
    (net (code "98") (name "unconnected-(TMC3-null-Pad10)") (class "Default")
      (node (ref "TMC3") (pin "10") (pinfunction "null_10") (pintype "passive"))
    )
    (net (code "99") (name "unconnected-(TMC4-MS1-Pad12)") (class "Default")
      (node (ref "TMC4") (pin "12") (pinfunction "MS1_12") (pintype "passive"))
    )
    (net (code "100") (name "unconnected-(TMC4-MS2-Pad13)") (class "Default")
      (node (ref "TMC4") (pin "13") (pinfunction "MS2_13") (pintype "passive"))
    )
    (net (code "101") (name "unconnected-(TMC4-NC-Pad16)") (class "Default")
      (node (ref "TMC4") (pin "16") (pinfunction "NC_16") (pintype "passive"))
    )
    (net (code "102") (name "unconnected-(TMC4-RX-Pad15)") (class "Default")
      (node (ref "TMC4") (pin "15") (pinfunction "RX_15") (pintype "passive"))
    )
    (net (code "103") (name "unconnected-(TMC4-TX-Pad14)") (class "Default")
      (node (ref "TMC4") (pin "14") (pinfunction "TX_14") (pintype "passive"))
    )
    (net (code "104") (name "unconnected-(TMC4-null-Pad9)") (class "Default")
      (node (ref "TMC4") (pin "9") (pinfunction "null_9") (pintype "passive"))
    )
    (net (code "105") (name "unconnected-(TMC4-null-Pad10)") (class "Default")
      (node (ref "TMC4") (pin "10") (pinfunction "null_10") (pintype "passive"))
    )
  )
)
